# CSR8675_Mini_System.net
KiCad netlist of a schematic drawn in EasyEDA Pro
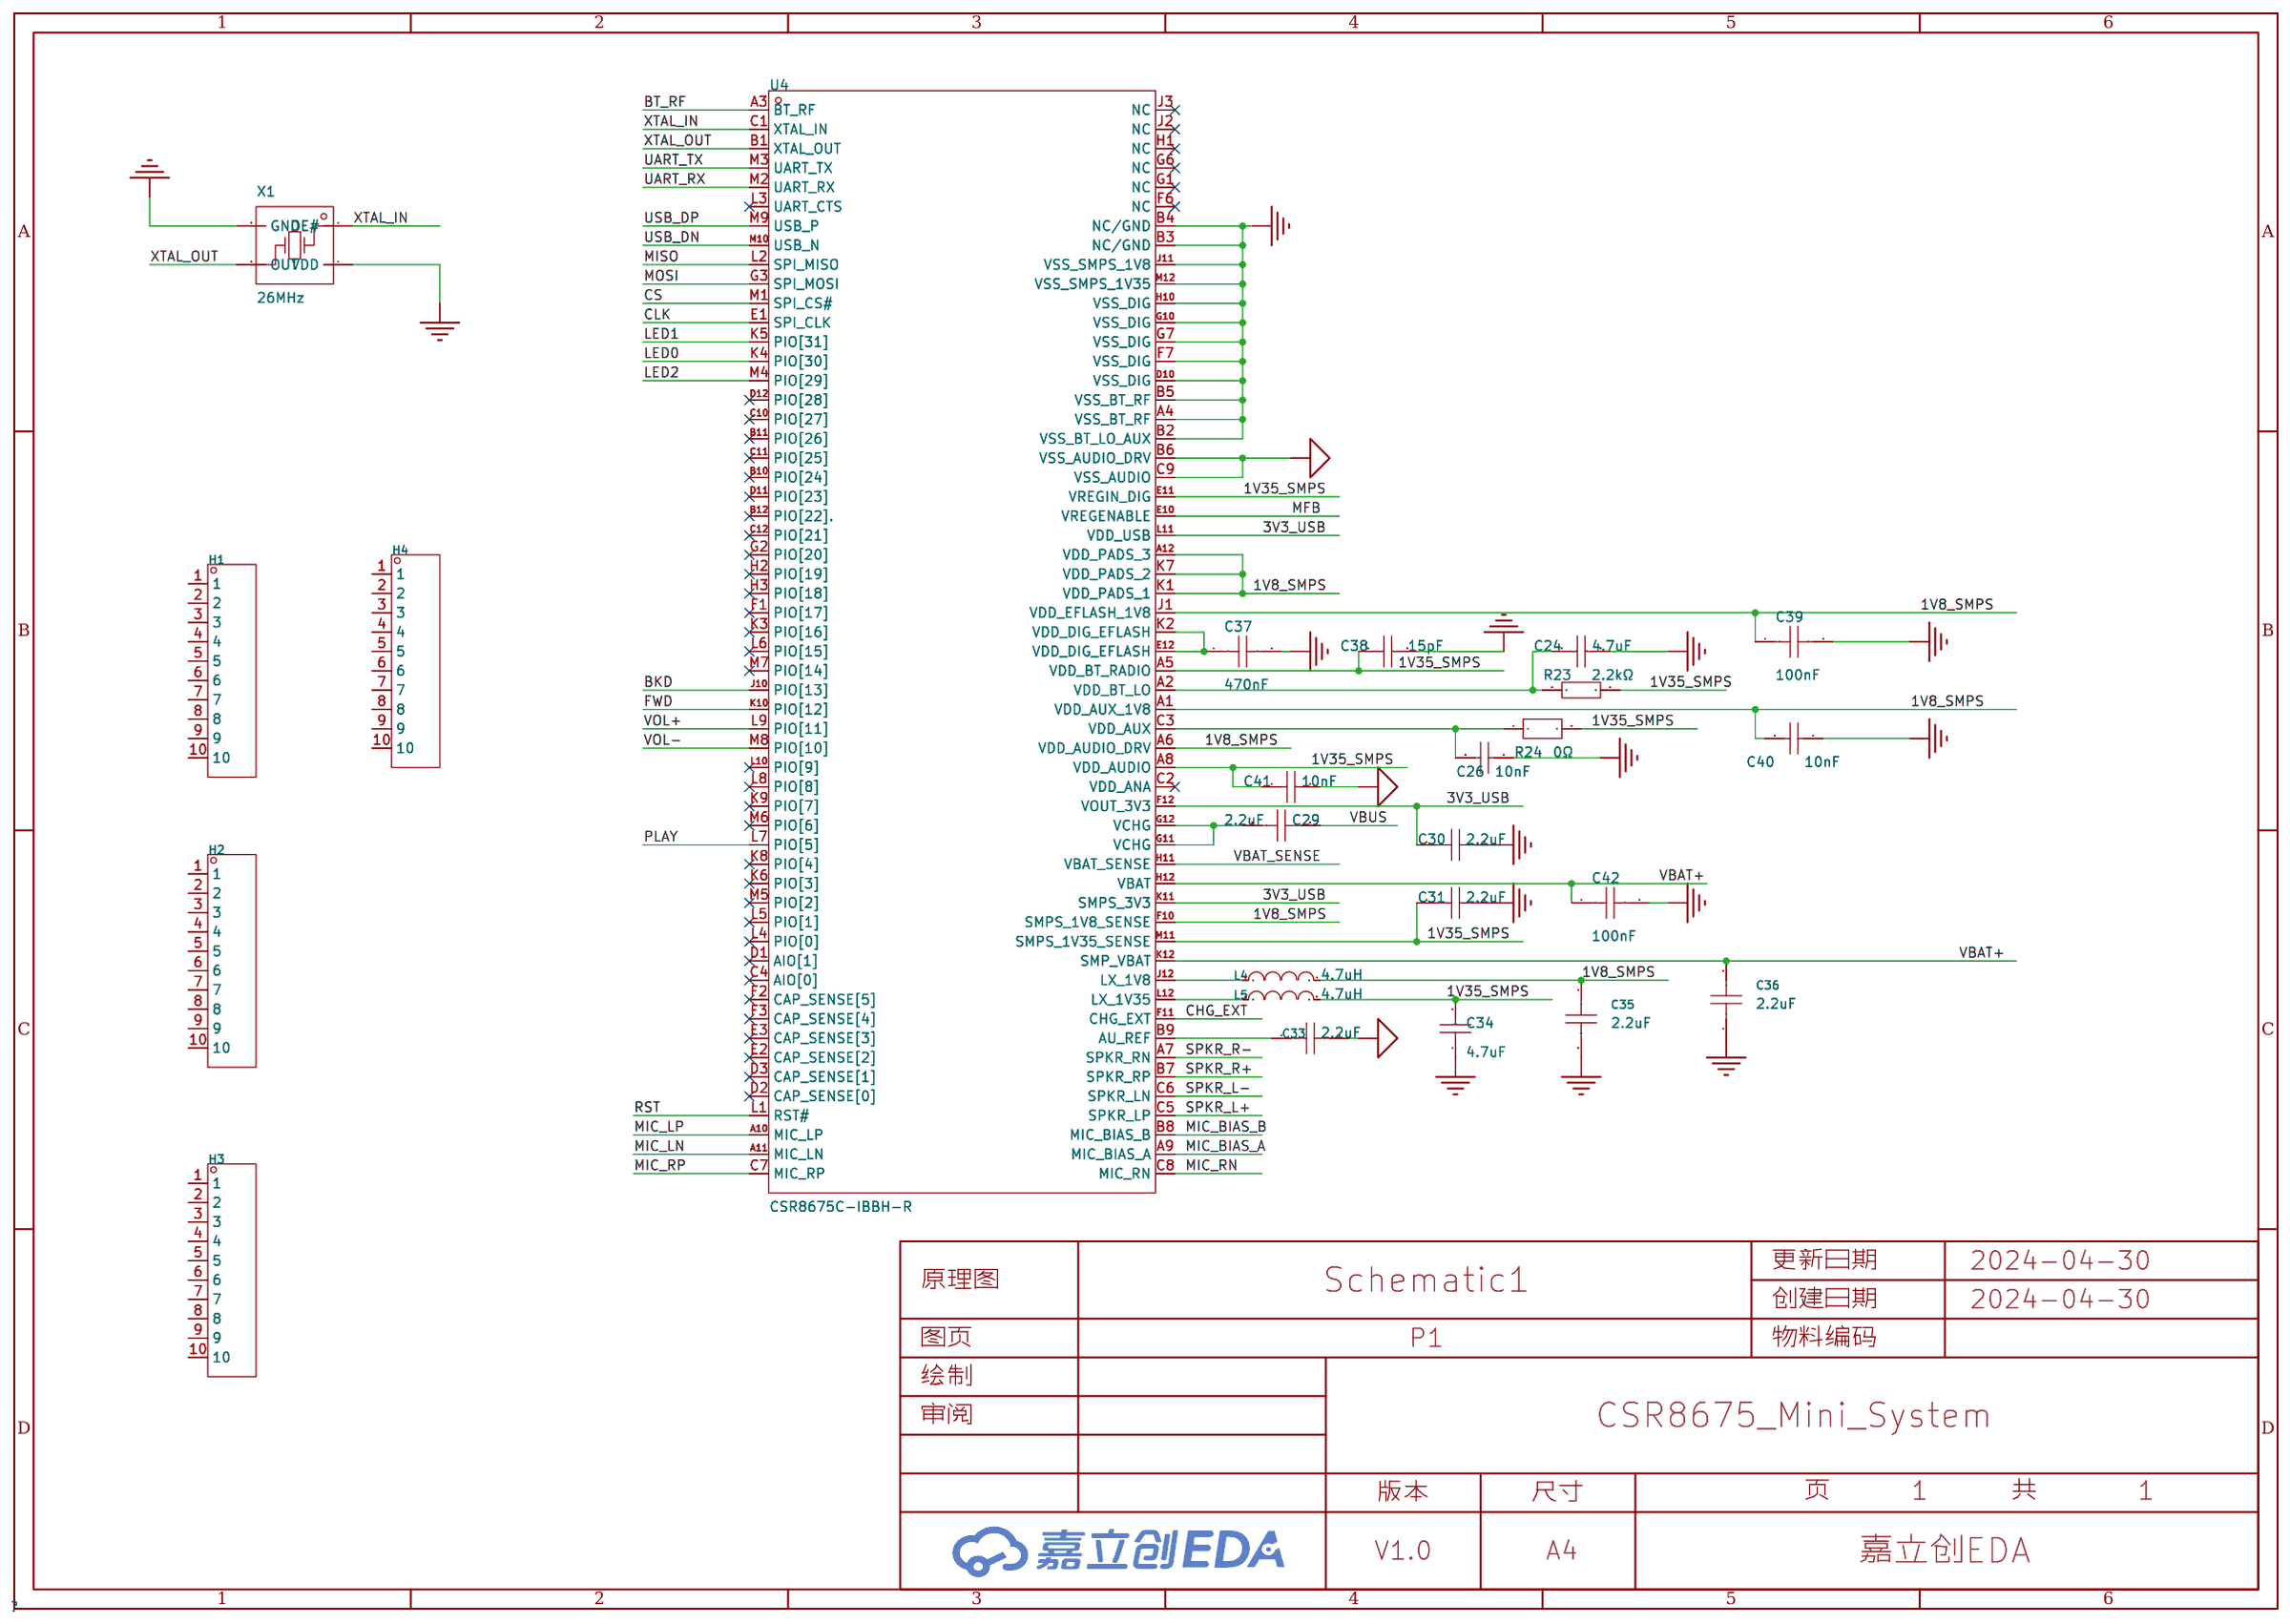
[diagram p0: schematic sheet]

(export (version "E")
  (design (tool "Eeschema 10.0.6"))
  (components
    (comp (ref "C24")
      (value "4.7uF")
      (footprint "easyedapro:C0603")
      (description "容值:4.7uF;精度:±10%;额定电压:16V;材质(温度系数):X5R;")
      (fields
        (field (name "Manufacturer Part") "CL10A475KO8NNNC")
        (field (name "Manufacturer") "SAMSUNG(三星)")
      )
      (libsource (lib "easyedapro") (part "CL10A475KO8NNNC"))
    )
    (comp (ref "C26")
      (value "10nF")
      (footprint "easyedapro:C0603")
      (description "容值:10nF;精度:±10%;额定电压:50V;材质(温度系数):X7R;")
      (fields
        (field (name "Manufacturer Part") "CC0603KRX7R9BB103")
        (field (name "Manufacturer") "YAGEO(国巨)")
      )
      (libsource (lib "easyedapro") (part "CC0603KRX7R9BB103"))
    )
    (comp (ref "C29")
      (value "2.2uF")
      (footprint "easyedapro:C0805")
      (description "容值:2.2uF;精度:±10%;额定电压:100V;材质(温度系数):X7T;")
      (fields
        (field (name "Manufacturer Part") "GRM21BD72A225KE01L")
        (field (name "Manufacturer") "muRata(村田)")
      )
      (libsource (lib "easyedapro") (part "GRM21BD72A225KE01L"))
    )
    (comp (ref "C30")
      (value "2.2uF")
      (footprint "easyedapro:C0805")
      (description "容值:2.2uF;精度:±10%;额定电压:100V;材质(温度系数):X7T;")
      (fields
        (field (name "Manufacturer Part") "GRM21BD72A225KE01L")
        (field (name "Manufacturer") "muRata(村田)")
      )
      (libsource (lib "easyedapro") (part "GRM21BD72A225KE01L"))
    )
    (comp (ref "C31")
      (value "2.2uF")
      (footprint "easyedapro:C0805")
      (description "容值:2.2uF;精度:±10%;额定电压:100V;材质(温度系数):X7T;")
      (fields
        (field (name "Manufacturer Part") "GRM21BD72A225KE01L")
        (field (name "Manufacturer") "muRata(村田)")
      )
      (libsource (lib "easyedapro") (part "GRM21BD72A225KE01L"))
    )
    (comp (ref "C33")
      (value "2.2uF")
      (footprint "easyedapro:C0603")
      (description "容值:2.2uF;精度:±10%;额定电压:50V;材质(温度系数):X5R;")
      (fields
        (field (name "Manufacturer Part") "CL10A225KB8NNNC")
        (field (name "Manufacturer") "SAMSUNG(三星)")
      )
      (libsource (lib "easyedapro") (part "CL10A225KB8NNNC"))
    )
    (comp (ref "C34")
      (value "4.7uF")
      (footprint "easyedapro:C0805")
      (description "容值:4.7uF;精度:±10%;额定电压:25V;材质(温度系数):X5R;")
      (fields
        (field (name "Manufacturer Part") "CL21A475KAQNNNE")
        (field (name "Manufacturer") "SAMSUNG(三星)")
      )
      (libsource (lib "easyedapro") (part "CL21A475KAQNNNE"))
    )
    (comp (ref "C35")
      (value "2.2uF")
      (footprint "easyedapro:C0603")
      (description "容值:2.2uF;精度:±10%;额定电压:50V;材质(温度系数):X5R;")
      (fields
        (field (name "Manufacturer Part") "CL10A225KB8NNNC")
        (field (name "Manufacturer") "SAMSUNG(三星)")
      )
      (libsource (lib "easyedapro") (part "CL10A225KB8NNNC"))
    )
    (comp (ref "C36")
      (value "2.2uF")
      (footprint "easyedapro:C0603")
      (description "容值:2.2uF;精度:±10%;额定电压:50V;材质(温度系数):X5R;")
      (fields
        (field (name "Manufacturer Part") "CL10A225KB8NNNC")
        (field (name "Manufacturer") "SAMSUNG(三星)")
      )
      (libsource (lib "easyedapro") (part "CL10A225KB8NNNC"))
    )
    (comp (ref "C37")
      (value "470nF")
      (footprint "easyedapro:C0402")
      (description "容值:470nF;精度:±10%;额定电压:50V;材质(温度系数):X5R;")
      (fields
        (field (name "Manufacturer Part") "GRM155R61H474KE11D")
        (field (name "Manufacturer") "muRata(村田)")
      )
      (libsource (lib "easyedapro") (part "GRM155R61H474KE11D"))
    )
    (comp (ref "C38")
      (value "15pF")
      (footprint "easyedapro:C0402")
      (description "容值:15pF;精度:±5%;额定电压:50V;材质(温度系数):C0G;")
      (fields (field (name "Manufacturer Part") "0402CG150J500NT") (field (name "Manufacturer") "FH(风华)"))
      (libsource (lib "easyedapro") (part "0402CG150J500NT"))
    )
    (comp (ref "C39")
      (value "100nF")
      (footprint "easyedapro:C0402")
      (description "容值:100nF;精度:±10%;额定电压:50V;材质(温度系数):X7R;")
      (fields
        (field (name "Manufacturer Part") "GRM155R71H104KE14D")
        (field (name "Manufacturer") "muRata(村田)")
      )
      (libsource (lib "easyedapro") (part "GRM155R71H104KE14D"))
    )
    (comp (ref "C40")
      (value "10nF")
      (footprint "easyedapro:C0402")
      (description "容值:10nF;精度:±10%;额定电压:50V;材质(温度系数):X7R;")
      (fields
        (field (name "Manufacturer Part") "CC0402KRX7R9BB103")
        (field (name "Manufacturer") "YAGEO(国巨)")
      )
      (libsource (lib "easyedapro") (part "CC0402KRX7R9BB103"))
    )
    (comp (ref "C41")
      (value "10nF")
      (footprint "easyedapro:C0402")
      (description "容值:10nF;精度:±10%;额定电压:50V;材质(温度系数):X7R;")
      (fields
        (field (name "Manufacturer Part") "CC0402KRX7R9BB103")
        (field (name "Manufacturer") "YAGEO(国巨)")
      )
      (libsource (lib "easyedapro") (part "CC0402KRX7R9BB103"))
    )
    (comp (ref "C42")
      (value "100nF")
      (footprint "easyedapro:C0402")
      (description "容值:100nF;精度:±10%;额定电压:50V;材质(温度系数):X7R;")
      (fields
        (field (name "Manufacturer Part") "GRM155R71H104KE14D")
        (field (name "Manufacturer") "muRata(村田)")
      )
      (libsource (lib "easyedapro") (part "GRM155R71H104KE14D"))
    )
    (comp (ref "H1")
      (value "~")
      (footprint "easyedapro:HDR-TH_10P-P2.54-V-M-1")
      (libsource (lib "easyedapro") (part "Header-Male-2.54_1x10"))
    )
    (comp (ref "H2")
      (value "~")
      (footprint "easyedapro:HDR-TH_10P-P2.54-V-M-1")
      (libsource (lib "easyedapro") (part "Header-Male-2.54_1x10"))
    )
    (comp (ref "H3")
      (value "~")
      (footprint "easyedapro:HDR-TH_10P-P2.54-V-M-1")
      (libsource (lib "easyedapro") (part "Header-Male-2.54_1x10"))
    )
    (comp (ref "H4")
      (value "~")
      (footprint "easyedapro:HDR-TH_10P-P2.54-V-M-1")
      (libsource (lib "easyedapro") (part "Header-Male-2.54_1x10"))
    )
    (comp (ref "L4")
      (value "4.7uH")
      (footprint "easyedapro:L0805")
      (description "电感值:4.7uH;精度:±20%;额定电流:800mA;饱和电流(Isat):-;直流电阻(DCR):288mΩ;")
      (fields (field (name "Manufacturer Part") "LQM21PN4R7MGRD") (field (name "Manufacturer") "muRata(村田)"))
      (libsource (lib "easyedapro") (part "LQM21PN4R7MGRD"))
    )
    (comp (ref "L5")
      (value "4.7uH")
      (footprint "easyedapro:L0805")
      (description "电感值:4.7uH;精度:±20%;额定电流:800mA;饱和电流(Isat):-;直流电阻(DCR):288mΩ;")
      (fields (field (name "Manufacturer Part") "LQM21PN4R7MGRD") (field (name "Manufacturer") "muRata(村田)"))
      (libsource (lib "easyedapro") (part "LQM21PN4R7MGRD"))
    )
    (comp (ref "R23")
      (value "2.2kΩ")
      (footprint "easyedapro:R0402")
      (description "电阻类型:厚膜电阻;阻值:2.2kΩ;精度:±1%;功率:62.5mW;最大工作电压:50V;温度系数:±100ppm/°C;")
      (fields
        (field (name "Manufacturer Part") "0402WGF2201TCE")
        (field (name "Manufacturer") "UNI-ROYAL(厚声)")
      )
      (libsource (lib "easyedapro") (part "0402WGF2201TCE"))
    )
    (comp (ref "R24")
      (value "0Ω")
      (footprint "easyedapro:R0402")
      (description "电阻类型:厚膜电阻;阻值:0Ω;精度:±1%;功率:62.5mW;最大工作电压:50V;")
      (fields (field (name "Manufacturer Part") "FRC0402F0000TS") (field (name "Manufacturer") "FOJAN(富捷)"))
      (libsource (lib "easyedapro") (part "FRC0402F0000TS"))
    )
    (comp (ref "U4")
      (value "CSR8675C-IBBH-R")
      (footprint "easyedapro:BGA-112_L6.5-W6.5-P0.50-TL")
      (description "频率范围:2.4GHz;接口:I2S;应用领域:蓝牙;灵敏度:-90dBm;")
      (fields (field (name "Manufacturer") "Qualcomm"))
      (libsource (lib "easyedapro") (part "CSR8675C-IBBH-R"))
    )
    (comp (ref "X1")
      (value "26MHz")
      (footprint "easyedapro:OSC-SMD_4P-L2.0-W1.6-BL_X201624MKB4SI")
      (description "频率:26MHz;工作电压:1.8V~3.3V;供电电流:4mA;频率稳定度(全温):±10ppm;")
      (fields (field (name "Manufacturer Part") "OT201626MJBA4SL") (field (name "Manufacturer") "YXC(扬兴晶振)"))
      (libsource (lib "easyedapro") (part "OT201626MJBA4SL"))
    )
  )
  (nets
    (net (code "1") (name "/1V8_SMPS") (class "Default")
      (node (ref "C35") (pin "1") (pinfunction "1_1") (pintype "input"))
      (node (ref "C39") (pin "1") (pinfunction "1_1") (pintype "unspecified"))
      (node (ref "C40") (pin "1") (pinfunction "1_1") (pintype "input"))
      (node (ref "L4") (pin "2") (pinfunction "2_2") (pintype "input"))
      (node (ref "U4") (pin "A1") (pinfunction "VDD_AUX_1V8_A1") (pintype "input"))
      (node (ref "U4") (pin "A12") (pinfunction "VDD_PADS_3_A12") (pintype "input"))
      (node (ref "U4") (pin "A6") (pinfunction "VDD_AUDIO_DRV_A6") (pintype "input"))
      (node (ref "U4") (pin "F10") (pinfunction "SMPS_1V8_SENSE_F10") (pintype "input"))
      (node (ref "U4") (pin "J1") (pinfunction "VDD_EFLASH_1V8_J1") (pintype "input"))
      (node (ref "U4") (pin "K1") (pinfunction "VDD_PADS_1_K1") (pintype "input"))
      (node (ref "U4") (pin "K7") (pinfunction "VDD_PADS_2_K7") (pintype "input"))
    )
    (net (code "2") (name "/1V35_SMPS") (class "Default")
      (node (ref "C31") (pin "1") (pinfunction "1_1") (pintype "unspecified"))
      (node (ref "C34") (pin "2") (pinfunction "2_2") (pintype "input"))
      (node (ref "C38") (pin "1") (pinfunction "1_1") (pintype "input"))
      (node (ref "C41") (pin "1") (pinfunction "1_1") (pintype "input"))
      (node (ref "L5") (pin "2") (pinfunction "2_2") (pintype "input"))
      (node (ref "R23") (pin "2") (pinfunction "2_2") (pintype "input"))
      (node (ref "R24") (pin "2") (pinfunction "2_2") (pintype "unspecified"))
      (node (ref "U4") (pin "A5") (pinfunction "VDD_BT_RADIO_A5") (pintype "input"))
      (node (ref "U4") (pin "A8") (pinfunction "VDD_AUDIO_A8") (pintype "input"))
      (node (ref "U4") (pin "E11") (pinfunction "VREGIN_DIG_E11") (pintype "input"))
      (node (ref "U4") (pin "M11") (pinfunction "SMPS_1V35_SENSE_M11") (pintype "input"))
    )
    (net (code "3") (name "/3V3_USB") (class "Default")
      (node (ref "C30") (pin "1") (pinfunction "1_1") (pintype "unspecified"))
      (node (ref "U4") (pin "F12") (pinfunction "VOUT_3V3_F12") (pintype "input"))
      (node (ref "U4") (pin "K11") (pinfunction "SMPS_3V3_K11") (pintype "input"))
      (node (ref "U4") (pin "L11") (pinfunction "VDD_USB_L11") (pintype "input"))
    )
    (net (code "4") (name "/BKD") (class "Default")
      (node (ref "U4") (pin "J10") (pinfunction "PIO[13]_J10") (pintype "input"))
    )
    (net (code "5") (name "/BT_RF") (class "Default")
      (node (ref "U4") (pin "A3") (pinfunction "BT_RF_A3") (pintype "input"))
    )
    (net (code "6") (name "/CHG_EXT") (class "Default")
      (node (ref "U4") (pin "F11") (pinfunction "CHG_EXT_F11") (pintype "input"))
    )
    (net (code "7") (name "/CLK") (class "Default")
      (node (ref "U4") (pin "E1") (pinfunction "SPI_CLK_E1") (pintype "input"))
    )
    (net (code "8") (name "/CS") (class "Default")
      (node (ref "U4") (pin "M1") (pinfunction "SPI_CS#_M1") (pintype "input"))
    )
    (net (code "9") (name "/FWD") (class "Default")
      (node (ref "U4") (pin "K10") (pinfunction "PIO[12]_K10") (pintype "input"))
    )
    (net (code "10") (name "/LED0") (class "Default")
      (node (ref "U4") (pin "K4") (pinfunction "PIO[30]_K4") (pintype "input"))
    )
    (net (code "11") (name "/LED1") (class "Default")
      (node (ref "U4") (pin "K5") (pinfunction "PIO[31]_K5") (pintype "input"))
    )
    (net (code "12") (name "/LED2") (class "Default")
      (node (ref "U4") (pin "M4") (pinfunction "PIO[29]_M4") (pintype "input"))
    )
    (net (code "13") (name "/MFB") (class "Default")
      (node (ref "U4") (pin "E10") (pinfunction "VREGENABLE_E10") (pintype "input"))
    )
    (net (code "14") (name "/MIC_BIAS_A") (class "Default")
      (node (ref "U4") (pin "A9") (pinfunction "MIC_BIAS_A_A9") (pintype "input"))
    )
    (net (code "15") (name "/MIC_BIAS_B") (class "Default")
      (node (ref "U4") (pin "B8") (pinfunction "MIC_BIAS_B_B8") (pintype "input"))
    )
    (net (code "16") (name "/MIC_LN") (class "Default")
      (node (ref "U4") (pin "A11") (pinfunction "MIC_LN_A11") (pintype "input"))
    )
    (net (code "17") (name "/MIC_LP") (class "Default")
      (node (ref "U4") (pin "A10") (pinfunction "MIC_LP_A10") (pintype "input"))
    )
    (net (code "18") (name "/MIC_RN") (class "Default")
      (node (ref "U4") (pin "C8") (pinfunction "MIC_RN_C8") (pintype "input"))
    )
    (net (code "19") (name "/MIC_RP") (class "Default")
      (node (ref "U4") (pin "C7") (pinfunction "MIC_RP_C7") (pintype "input"))
    )
    (net (code "20") (name "/MISO") (class "Default")
      (node (ref "U4") (pin "L2") (pinfunction "SPI_MISO_L2") (pintype "input"))
    )
    (net (code "21") (name "/MOSI") (class "Default")
      (node (ref "U4") (pin "G3") (pinfunction "SPI_MOSI_G3") (pintype "input"))
    )
    (net (code "22") (name "/PLAY") (class "Default")
      (node (ref "U4") (pin "L7") (pinfunction "PIO[5]_L7") (pintype "input"))
    )
    (net (code "23") (name "/RST") (class "Default")
      (node (ref "U4") (pin "L1") (pinfunction "RST#_L1") (pintype "input"))
    )
    (net (code "24") (name "/SPKR_L+") (class "Default")
      (node (ref "U4") (pin "C5") (pinfunction "SPKR_LP_C5") (pintype "input"))
    )
    (net (code "25") (name "/SPKR_L-") (class "Default")
      (node (ref "U4") (pin "C6") (pinfunction "SPKR_LN_C6") (pintype "input"))
    )
    (net (code "26") (name "/SPKR_R+") (class "Default")
      (node (ref "U4") (pin "B7") (pinfunction "SPKR_RP_B7") (pintype "input"))
    )
    (net (code "27") (name "/SPKR_R-") (class "Default")
      (node (ref "U4") (pin "A7") (pinfunction "SPKR_RN_A7") (pintype "input"))
    )
    (net (code "28") (name "/UART_RX") (class "Default")
      (node (ref "U4") (pin "M2") (pinfunction "UART_RX_M2") (pintype "input"))
    )
    (net (code "29") (name "/UART_TX") (class "Default")
      (node (ref "U4") (pin "M3") (pinfunction "UART_TX_M3") (pintype "input"))
    )
    (net (code "30") (name "/USB_DN") (class "Default")
      (node (ref "U4") (pin "M10") (pinfunction "USB_N_M10") (pintype "input"))
    )
    (net (code "31") (name "/USB_DP") (class "Default")
      (node (ref "U4") (pin "M9") (pinfunction "USB_P_M9") (pintype "input"))
    )
    (net (code "32") (name "/VBAT+") (class "Default")
      (node (ref "C36") (pin "2") (pinfunction "2_2") (pintype "input"))
      (node (ref "C42") (pin "1") (pinfunction "1_1") (pintype "unspecified"))
      (node (ref "U4") (pin "H12") (pinfunction "VBAT_H12") (pintype "input"))
      (node (ref "U4") (pin "K12") (pinfunction "SMP_VBAT_K12") (pintype "input"))
    )
    (net (code "33") (name "/VBAT_SENSE") (class "Default")
      (node (ref "U4") (pin "H11") (pinfunction "VBAT_SENSE_H11") (pintype "input"))
    )
    (net (code "34") (name "/VBUS") (class "Default")
      (node (ref "C29") (pin "2") (pinfunction "2_2") (pintype "unspecified"))
    )
    (net (code "35") (name "/VOL+") (class "Default")
      (node (ref "U4") (pin "L9") (pinfunction "PIO[11]_L9") (pintype "input"))
    )
    (net (code "36") (name "/VOL-") (class "Default")
      (node (ref "U4") (pin "M8") (pinfunction "PIO[10]_M8") (pintype "input"))
    )
    (net (code "37") (name "/XTAL_IN") (class "Default")
      (node (ref "U4") (pin "C1") (pinfunction "XTAL_IN_C1") (pintype "input"))
      (node (ref "X1") (pin "1") (pinfunction "OE#_1") (pintype "input"))
    )
    (net (code "38") (name "/XTAL_OUT") (class "Default")
      (node (ref "U4") (pin "B1") (pinfunction "XTAL_OUT_B1") (pintype "input"))
      (node (ref "X1") (pin "3") (pinfunction "OUT_3") (pintype "input"))
    )
    (net (code "39") (name "AGND") (class "Default")
      (node (ref "C33") (pin "2") (pinfunction "2_2") (pintype "input"))
      (node (ref "C41") (pin "2") (pinfunction "2_2") (pintype "input"))
      (node (ref "U4") (pin "B6") (pinfunction "VSS_AUDIO_DRV_B6") (pintype "input"))
      (node (ref "U4") (pin "C9") (pinfunction "VSS_AUDIO_C9") (pintype "input"))
    )
    (net (code "40") (name "GND") (class "Default")
      (node (ref "C24") (pin "2") (pinfunction "2_2") (pintype "input"))
      (node (ref "C26") (pin "1") (pinfunction "1_1") (pintype "input"))
      (node (ref "C30") (pin "2") (pinfunction "2_2") (pintype "unspecified"))
      (node (ref "C31") (pin "2") (pinfunction "2_2") (pintype "unspecified"))
      (node (ref "C34") (pin "1") (pinfunction "1_1") (pintype "input"))
      (node (ref "C35") (pin "2") (pinfunction "2_2") (pintype "input"))
      (node (ref "C36") (pin "1") (pinfunction "1_1") (pintype "input"))
      (node (ref "C37") (pin "2") (pinfunction "2_2") (pintype "unspecified"))
      (node (ref "C38") (pin "2") (pinfunction "2_2") (pintype "input"))
      (node (ref "C39") (pin "2") (pinfunction "2_2") (pintype "unspecified"))
      (node (ref "C40") (pin "2") (pinfunction "2_2") (pintype "input"))
      (node (ref "C42") (pin "2") (pinfunction "2_2") (pintype "unspecified"))
      (node (ref "U4") (pin "A4") (pinfunction "VSS_BT_RF_A4") (pintype "input"))
      (node (ref "U4") (pin "B2") (pinfunction "VSS_BT_LO_AUX_B2") (pintype "input"))
      (node (ref "U4") (pin "B3") (pinfunction "NC/GND_B3") (pintype "input"))
      (node (ref "U4") (pin "B4") (pinfunction "NC/GND_B4") (pintype "input"))
      (node (ref "U4") (pin "B5") (pinfunction "VSS_BT_RF_B5") (pintype "input"))
      (node (ref "U4") (pin "D10") (pinfunction "VSS_DIG_D10") (pintype "input"))
      (node (ref "U4") (pin "F7") (pinfunction "VSS_DIG_F7") (pintype "input"))
      (node (ref "U4") (pin "G10") (pinfunction "VSS_DIG_G10") (pintype "input"))
      (node (ref "U4") (pin "G7") (pinfunction "VSS_DIG_G7") (pintype "input"))
      (node (ref "U4") (pin "H10") (pinfunction "VSS_DIG_H10") (pintype "input"))
      (node (ref "U4") (pin "J11") (pinfunction "VSS_SMPS_1V8_J11") (pintype "input"))
      (node (ref "U4") (pin "M12") (pinfunction "VSS_SMPS_1V35_M12") (pintype "input"))
      (node (ref "X1") (pin "2") (pinfunction "GND_2") (pintype "input"))
      (node (ref "X1") (pin "4") (pinfunction "VDD_4") (pintype "input"))
    )
    (net (code "41") (name "Net-(C29-Pad1)") (class "Default")
      (node (ref "C29") (pin "1") (pinfunction "1_1") (pintype "unspecified"))
      (node (ref "U4") (pin "G11") (pinfunction "VCHG_G11") (pintype "input"))
      (node (ref "U4") (pin "G12") (pinfunction "VCHG_G12") (pintype "input"))
    )
    (net (code "42") (name "Net-(C37-Pad1)") (class "Default")
      (node (ref "C37") (pin "1") (pinfunction "1_1") (pintype "unspecified"))
      (node (ref "U4") (pin "E12") (pinfunction "VDD_DIG_EFLASH_E12") (pintype "input"))
      (node (ref "U4") (pin "K2") (pinfunction "VDD_DIG_EFLASH_K2") (pintype "input"))
    )
    (net (code "43") (name "Net-(U4-AU_REF)") (class "Default")
      (node (ref "C33") (pin "1") (pinfunction "1_1") (pintype "input"))
      (node (ref "U4") (pin "B9") (pinfunction "AU_REF_B9") (pintype "input"))
    )
    (net (code "44") (name "Net-(U4-LX_1V8)") (class "Default")
      (node (ref "L4") (pin "1") (pinfunction "1_1") (pintype "input"))
      (node (ref "U4") (pin "J12") (pinfunction "LX_1V8_J12") (pintype "input"))
    )
    (net (code "45") (name "Net-(U4-LX_1V35)") (class "Default")
      (node (ref "L5") (pin "1") (pinfunction "1_1") (pintype "input"))
      (node (ref "U4") (pin "L12") (pinfunction "LX_1V35_L12") (pintype "input"))
    )
    (net (code "46") (name "Net-(U4-VDD_AUX)") (class "Default")
      (node (ref "C26") (pin "2") (pinfunction "2_2") (pintype "input"))
      (node (ref "R24") (pin "1") (pinfunction "1_1") (pintype "unspecified"))
      (node (ref "U4") (pin "C3") (pinfunction "VDD_AUX_C3") (pintype "input"))
    )
    (net (code "47") (name "Net-(U4-VDD_BT_LO)") (class "Default")
      (node (ref "C24") (pin "1") (pinfunction "1_1") (pintype "input"))
      (node (ref "R23") (pin "1") (pinfunction "1_1") (pintype "input"))
      (node (ref "U4") (pin "A2") (pinfunction "VDD_BT_LO_A2") (pintype "input"))
    )
    (net (code "48") (name "unconnected-(H1-Pad1)") (class "Default")
      (node (ref "H1") (pin "1") (pinfunction "1_1") (pintype "input"))
    )
    (net (code "49") (name "unconnected-(H1-Pad2)") (class "Default")
      (node (ref "H1") (pin "2") (pinfunction "2_2") (pintype "input"))
    )
    (net (code "50") (name "unconnected-(H1-Pad3)") (class "Default")
      (node (ref "H1") (pin "3") (pinfunction "3_3") (pintype "input"))
    )
    (net (code "51") (name "unconnected-(H1-Pad4)") (class "Default")
      (node (ref "H1") (pin "4") (pinfunction "4_4") (pintype "input"))
    )
    (net (code "52") (name "unconnected-(H1-Pad5)") (class "Default")
      (node (ref "H1") (pin "5") (pinfunction "5_5") (pintype "input"))
    )
    (net (code "53") (name "unconnected-(H1-Pad6)") (class "Default")
      (node (ref "H1") (pin "6") (pinfunction "6_6") (pintype "input"))
    )
    (net (code "54") (name "unconnected-(H1-Pad7)") (class "Default")
      (node (ref "H1") (pin "7") (pinfunction "7_7") (pintype "input"))
    )
    (net (code "55") (name "unconnected-(H1-Pad8)") (class "Default")
      (node (ref "H1") (pin "8") (pinfunction "8_8") (pintype "input"))
    )
    (net (code "56") (name "unconnected-(H1-Pad9)") (class "Default")
      (node (ref "H1") (pin "9") (pinfunction "9_9") (pintype "input"))
    )
    (net (code "57") (name "unconnected-(H1-Pad10)") (class "Default")
      (node (ref "H1") (pin "10") (pinfunction "10_10") (pintype "input"))
    )
    (net (code "58") (name "unconnected-(H2-Pad1)") (class "Default")
      (node (ref "H2") (pin "1") (pinfunction "1_1") (pintype "input"))
    )
    (net (code "59") (name "unconnected-(H2-Pad2)") (class "Default")
      (node (ref "H2") (pin "2") (pinfunction "2_2") (pintype "input"))
    )
    (net (code "60") (name "unconnected-(H2-Pad3)") (class "Default")
      (node (ref "H2") (pin "3") (pinfunction "3_3") (pintype "input"))
    )
    (net (code "61") (name "unconnected-(H2-Pad4)") (class "Default")
      (node (ref "H2") (pin "4") (pinfunction "4_4") (pintype "input"))
    )
    (net (code "62") (name "unconnected-(H2-Pad5)") (class "Default")
      (node (ref "H2") (pin "5") (pinfunction "5_5") (pintype "input"))
    )
    (net (code "63") (name "unconnected-(H2-Pad6)") (class "Default")
      (node (ref "H2") (pin "6") (pinfunction "6_6") (pintype "input"))
    )
    (net (code "64") (name "unconnected-(H2-Pad7)") (class "Default")
      (node (ref "H2") (pin "7") (pinfunction "7_7") (pintype "input"))
    )
    (net (code "65") (name "unconnected-(H2-Pad8)") (class "Default")
      (node (ref "H2") (pin "8") (pinfunction "8_8") (pintype "input"))
    )
    (net (code "66") (name "unconnected-(H2-Pad9)") (class "Default")
      (node (ref "H2") (pin "9") (pinfunction "9_9") (pintype "input"))
    )
    (net (code "67") (name "unconnected-(H2-Pad10)") (class "Default")
      (node (ref "H2") (pin "10") (pinfunction "10_10") (pintype "input"))
    )
    (net (code "68") (name "unconnected-(H3-Pad1)") (class "Default")
      (node (ref "H3") (pin "1") (pinfunction "1_1") (pintype "input"))
    )
    (net (code "69") (name "unconnected-(H3-Pad2)") (class "Default")
      (node (ref "H3") (pin "2") (pinfunction "2_2") (pintype "input"))
    )
    (net (code "70") (name "unconnected-(H3-Pad3)") (class "Default")
      (node (ref "H3") (pin "3") (pinfunction "3_3") (pintype "input"))
    )
    (net (code "71") (name "unconnected-(H3-Pad4)") (class "Default")
      (node (ref "H3") (pin "4") (pinfunction "4_4") (pintype "input"))
    )
    (net (code "72") (name "unconnected-(H3-Pad5)") (class "Default")
      (node (ref "H3") (pin "5") (pinfunction "5_5") (pintype "input"))
    )
    (net (code "73") (name "unconnected-(H3-Pad6)") (class "Default")
      (node (ref "H3") (pin "6") (pinfunction "6_6") (pintype "input"))
    )
    (net (code "74") (name "unconnected-(H3-Pad7)") (class "Default")
      (node (ref "H3") (pin "7") (pinfunction "7_7") (pintype "input"))
    )
    (net (code "75") (name "unconnected-(H3-Pad8)") (class "Default")
      (node (ref "H3") (pin "8") (pinfunction "8_8") (pintype "input"))
    )
    (net (code "76") (name "unconnected-(H3-Pad9)") (class "Default")
      (node (ref "H3") (pin "9") (pinfunction "9_9") (pintype "input"))
    )
    (net (code "77") (name "unconnected-(H3-Pad10)") (class "Default")
      (node (ref "H3") (pin "10") (pinfunction "10_10") (pintype "input"))
    )
    (net (code "78") (name "unconnected-(H4-Pad1)") (class "Default")
      (node (ref "H4") (pin "1") (pinfunction "1_1") (pintype "input"))
    )
    (net (code "79") (name "unconnected-(H4-Pad2)") (class "Default")
      (node (ref "H4") (pin "2") (pinfunction "2_2") (pintype "input"))
    )
    (net (code "80") (name "unconnected-(H4-Pad3)") (class "Default")
      (node (ref "H4") (pin "3") (pinfunction "3_3") (pintype "input"))
    )
    (net (code "81") (name "unconnected-(H4-Pad4)") (class "Default")
      (node (ref "H4") (pin "4") (pinfunction "4_4") (pintype "input"))
    )
    (net (code "82") (name "unconnected-(H4-Pad5)") (class "Default")
      (node (ref "H4") (pin "5") (pinfunction "5_5") (pintype "input"))
    )
    (net (code "83") (name "unconnected-(H4-Pad6)") (class "Default")
      (node (ref "H4") (pin "6") (pinfunction "6_6") (pintype "input"))
    )
    (net (code "84") (name "unconnected-(H4-Pad7)") (class "Default")
      (node (ref "H4") (pin "7") (pinfunction "7_7") (pintype "input"))
    )
    (net (code "85") (name "unconnected-(H4-Pad8)") (class "Default")
      (node (ref "H4") (pin "8") (pinfunction "8_8") (pintype "input"))
    )
    (net (code "86") (name "unconnected-(H4-Pad9)") (class "Default")
      (node (ref "H4") (pin "9") (pinfunction "9_9") (pintype "input"))
    )
    (net (code "87") (name "unconnected-(H4-Pad10)") (class "Default")
      (node (ref "H4") (pin "10") (pinfunction "10_10") (pintype "input"))
    )
    (net (code "88") (name "unconnected-(U4-AIO[0]-PadC4)") (class "Default")
      (node (ref "U4") (pin "C4") (pinfunction "AIO[0]_C4") (pintype "input+no_connect"))
    )
    (net (code "89") (name "unconnected-(U4-AIO[1]-PadD1)") (class "Default")
      (node (ref "U4") (pin "D1") (pinfunction "AIO[1]_D1") (pintype "input+no_connect"))
    )
    (net (code "90") (name "unconnected-(U4-CAP_SENSE[0]-PadD2)") (class "Default")
      (node (ref "U4") (pin "D2") (pinfunction "CAP_SENSE[0]_D2") (pintype "input+no_connect"))
    )
    (net (code "91") (name "unconnected-(U4-CAP_SENSE[1]-PadD3)") (class "Default")
      (node (ref "U4") (pin "D3") (pinfunction "CAP_SENSE[1]_D3") (pintype "input+no_connect"))
    )
    (net (code "92") (name "unconnected-(U4-CAP_SENSE[2]-PadE2)") (class "Default")
      (node (ref "U4") (pin "E2") (pinfunction "CAP_SENSE[2]_E2") (pintype "input+no_connect"))
    )
    (net (code "93") (name "unconnected-(U4-CAP_SENSE[3]-PadE3)") (class "Default")
      (node (ref "U4") (pin "E3") (pinfunction "CAP_SENSE[3]_E3") (pintype "input+no_connect"))
    )
    (net (code "94") (name "unconnected-(U4-CAP_SENSE[4]-PadF3)") (class "Default")
      (node (ref "U4") (pin "F3") (pinfunction "CAP_SENSE[4]_F3") (pintype "input+no_connect"))
    )
    (net (code "95") (name "unconnected-(U4-CAP_SENSE[5]-PadF2)") (class "Default")
      (node (ref "U4") (pin "F2") (pinfunction "CAP_SENSE[5]_F2") (pintype "input+no_connect"))
    )
    (net (code "96") (name "unconnected-(U4-NC-PadF6)") (class "Default")
      (node (ref "U4") (pin "F6") (pinfunction "NC_F6") (pintype "input+no_connect"))
    )
    (net (code "97") (name "unconnected-(U4-NC-PadG1)") (class "Default")
      (node (ref "U4") (pin "G1") (pinfunction "NC_G1") (pintype "input+no_connect"))
    )
    (net (code "98") (name "unconnected-(U4-NC-PadG6)") (class "Default")
      (node (ref "U4") (pin "G6") (pinfunction "NC_G6") (pintype "input+no_connect"))
    )
    (net (code "99") (name "unconnected-(U4-NC-PadH1)") (class "Default")
      (node (ref "U4") (pin "H1") (pinfunction "NC_H1") (pintype "input+no_connect"))
    )
    (net (code "100") (name "unconnected-(U4-NC-PadJ2)") (class "Default")
      (node (ref "U4") (pin "J2") (pinfunction "NC_J2") (pintype "input+no_connect"))
    )
    (net (code "101") (name "unconnected-(U4-NC-PadJ3)") (class "Default")
      (node (ref "U4") (pin "J3") (pinfunction "NC_J3") (pintype "input+no_connect"))
    )
    (net (code "102") (name "unconnected-(U4-PIO[0]-PadL4)") (class "Default")
      (node (ref "U4") (pin "L4") (pinfunction "PIO[0]_L4") (pintype "input+no_connect"))
    )
    (net (code "103") (name "unconnected-(U4-PIO[1]-PadL5)") (class "Default")
      (node (ref "U4") (pin "L5") (pinfunction "PIO[1]_L5") (pintype "input+no_connect"))
    )
    (net (code "104") (name "unconnected-(U4-PIO[2]-PadM5)") (class "Default")
      (node (ref "U4") (pin "M5") (pinfunction "PIO[2]_M5") (pintype "input+no_connect"))
    )
    (net (code "105") (name "unconnected-(U4-PIO[3]-PadK6)") (class "Default")
      (node (ref "U4") (pin "K6") (pinfunction "PIO[3]_K6") (pintype "input+no_connect"))
    )
    (net (code "106") (name "unconnected-(U4-PIO[4]-PadK8)") (class "Default")
      (node (ref "U4") (pin "K8") (pinfunction "PIO[4]_K8") (pintype "input+no_connect"))
    )
    (net (code "107") (name "unconnected-(U4-PIO[6]-PadM6)") (class "Default")
      (node (ref "U4") (pin "M6") (pinfunction "PIO[6]_M6") (pintype "input+no_connect"))
    )
    (net (code "108") (name "unconnected-(U4-PIO[7]-PadK9)") (class "Default")
      (node (ref "U4") (pin "K9") (pinfunction "PIO[7]_K9") (pintype "input+no_connect"))
    )
    (net (code "109") (name "unconnected-(U4-PIO[8]-PadL8)") (class "Default")
      (node (ref "U4") (pin "L8") (pinfunction "PIO[8]_L8") (pintype "input+no_connect"))
    )
    (net (code "110") (name "unconnected-(U4-PIO[9]-PadL10)") (class "Default")
      (node (ref "U4") (pin "L10") (pinfunction "PIO[9]_L10") (pintype "input+no_connect"))
    )
    (net (code "111") (name "unconnected-(U4-PIO[14]-PadM7)") (class "Default")
      (node (ref "U4") (pin "M7") (pinfunction "PIO[14]_M7") (pintype "input+no_connect"))
    )
    (net (code "112") (name "unconnected-(U4-PIO[15]-PadL6)") (class "Default")
      (node (ref "U4") (pin "L6") (pinfunction "PIO[15]_L6") (pintype "input+no_connect"))
    )
    (net (code "113") (name "unconnected-(U4-PIO[16]-PadK3)") (class "Default")
      (node (ref "U4") (pin "K3") (pinfunction "PIO[16]_K3") (pintype "input+no_connect"))
    )
    (net (code "114") (name "unconnected-(U4-PIO[17]-PadF1)") (class "Default")
      (node (ref "U4") (pin "F1") (pinfunction "PIO[17]_F1") (pintype "input+no_connect"))
    )
    (net (code "115") (name "unconnected-(U4-PIO[18]-PadH3)") (class "Default")
      (node (ref "U4") (pin "H3") (pinfunction "PIO[18]_H3") (pintype "input+no_connect"))
    )
    (net (code "116") (name "unconnected-(U4-PIO[19]-PadH2)") (class "Default")
      (node (ref "U4") (pin "H2") (pinfunction "PIO[19]_H2") (pintype "input+no_connect"))
    )
    (net (code "117") (name "unconnected-(U4-PIO[20]-PadG2)") (class "Default")
      (node (ref "U4") (pin "G2") (pinfunction "PIO[20]_G2") (pintype "input+no_connect"))
    )
    (net (code "118") (name "unconnected-(U4-PIO[21]-PadC12)") (class "Default")
      (node (ref "U4") (pin "C12") (pinfunction "PIO[21]_C12") (pintype "input+no_connect"))
    )
    (net (code "119") (name "unconnected-(U4-PIO[22].-PadB12)") (class "Default")
      (node (ref "U4") (pin "B12") (pinfunction "PIO[22]._B12") (pintype "input+no_connect"))
    )
    (net (code "120") (name "unconnected-(U4-PIO[23]-PadD11)") (class "Default")
      (node (ref "U4") (pin "D11") (pinfunction "PIO[23]_D11") (pintype "input+no_connect"))
    )
    (net (code "121") (name "unconnected-(U4-PIO[24]-PadB10)") (class "Default")
      (node (ref "U4") (pin "B10") (pinfunction "PIO[24]_B10") (pintype "input+no_connect"))
    )
    (net (code "122") (name "unconnected-(U4-PIO[25]-PadC11)") (class "Default")
      (node (ref "U4") (pin "C11") (pinfunction "PIO[25]_C11") (pintype "input+no_connect"))
    )
    (net (code "123") (name "unconnected-(U4-PIO[26]-PadB11)") (class "Default")
      (node (ref "U4") (pin "B11") (pinfunction "PIO[26]_B11") (pintype "input+no_connect"))
    )
    (net (code "124") (name "unconnected-(U4-PIO[27]-PadC10)") (class "Default")
      (node (ref "U4") (pin "C10") (pinfunction "PIO[27]_C10") (pintype "input+no_connect"))
    )
    (net (code "125") (name "unconnected-(U4-PIO[28]-PadD12)") (class "Default")
      (node (ref "U4") (pin "D12") (pinfunction "PIO[28]_D12") (pintype "input+no_connect"))
    )
    (net (code "126") (name "unconnected-(U4-UART_CTS-PadL3)") (class "Default")
      (node (ref "U4") (pin "L3") (pinfunction "UART_CTS_L3") (pintype "input+no_connect"))
    )
    (net (code "127") (name "unconnected-(U4-VDD_ANA-PadC2)") (class "Default")
      (node (ref "U4") (pin "C2") (pinfunction "VDD_ANA_C2") (pintype "input+no_connect"))
    )
  )
)
